# Sheet1.net
KiCad netlist of a schematic drawn in Altium Designer
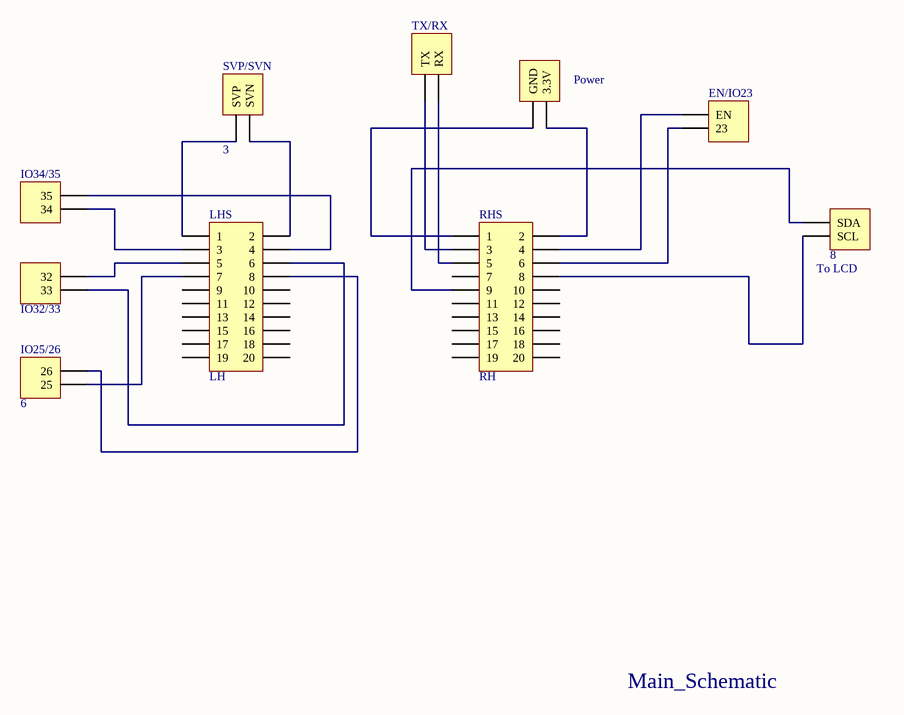
[diagram p0: Sheet1.SchDoc]

(export (version "E")
  (design (tool "Eeschema 10.0.6"))
  (components
    (comp (ref "EN/IO23")
      (value "7")
      (footprint "HDR1X2")
      (description "Header, 2-Pin")
      (fields (field (name "PUBLISHER") "Altium Limited"))
      (libsource (lib "") (part "Header 2H_3"))
    )
    (comp (ref "IO25/26")
      (value "6")
      (footprint "HDR1X2")
      (description "Header, 2-Pin")
      (fields (field (name "PUBLISHER") "Altium Limited"))
      (libsource (lib "") (part "Header 2H_4"))
    )
    (comp (ref "IO32/33")
      (value "5")
      (footprint "HDR1X2")
      (description "Header, 2-Pin")
      (fields (field (name "PUBLISHER") "Altium Limited"))
      (libsource (lib "") (part "Header 2H_4"))
    )
    (comp (ref "IO34/35")
      (value "4")
      (footprint "HDR1X2")
      (description "Header, 2-Pin")
      (fields (field (name "PUBLISHER") "Altium Limited"))
      (libsource (lib "") (part "Header 2H_4"))
    )
    (comp (ref "LHS")
      (value "LH")
      (footprint "HDR2X10")
      (description "Header, 10-Pin, Dual row")
      (fields (field (name "PUBLISHER") "Altium Limited"))
      (libsource (lib "University of Moratuwa") (part "Header 10X2H"))
    )
    (comp (ref "Power")
      (value "1")
      (footprint "HDR1X2")
      (description "Header, 2-Pin")
      (fields (field (name "PUBLISHER") "Altium Limited"))
      (libsource (lib "") (part "Header 2H_5"))
    )
    (comp (ref "RHS")
      (value "RH")
      (footprint "HDR2X10")
      (description "Header, 10-Pin, Dual row")
      (fields (field (name "PUBLISHER") "Altium Limited"))
      (libsource (lib "University of Moratuwa") (part "Header 10X2H"))
    )
    (comp (ref "SVP/SVN")
      (value "3")
      (footprint "HDR1X2")
      (description "Header, 2-Pin")
      (fields (field (name "PUBLISHER") "Altium Limited"))
      (libsource (lib "") (part "Header 2H_2"))
    )
    (comp (ref "To LCD")
      (value "8")
      (footprint "HDR1X2")
      (description "Header, 2-Pin")
      (fields (field (name "PUBLISHER") "Altium Limited"))
      (libsource (lib "University of Moratuwa") (part "Header 2H"))
    )
    (comp (ref "TX/RX")
      (value "2")
      (footprint "HDR1X2")
      (description "Header, 2-Pin")
      (fields (field (name "PUBLISHER") "Altium Limited"))
      (libsource (lib "") (part "Header 2H_1"))
    )
  )
  (nets
    (net (code "1") (name "Net-(EN/IO23-23)") (class "Default")
      (node (ref "EN/IO23") (pin "2") (pinfunction "23_2") (pintype "passive"))
      (node (ref "RHS") (pin "6") (pinfunction "6_6") (pintype "passive"))
    )
    (net (code "2") (name "Net-(EN/IO23-EN)") (class "Default")
      (node (ref "EN/IO23") (pin "1") (pinfunction "EN_1") (pintype "passive"))
      (node (ref "RHS") (pin "4") (pinfunction "4_4") (pintype "passive"))
    )
    (net (code "3") (name "Net-(IO25/26-25)") (class "Default")
      (node (ref "IO25/26") (pin "1") (pinfunction "25_1") (pintype "passive"))
      (node (ref "LHS") (pin "7") (pinfunction "7_7") (pintype "passive"))
    )
    (net (code "4") (name "Net-(IO25/26-26)") (class "Default")
      (node (ref "IO25/26") (pin "2") (pinfunction "26_2") (pintype "passive"))
      (node (ref "LHS") (pin "8") (pinfunction "8_8") (pintype "passive"))
    )
    (net (code "5") (name "Net-(IO32/33-25)") (class "Default")
      (node (ref "IO32/33") (pin "1") (pinfunction "25_1") (pintype "passive"))
      (node (ref "LHS") (pin "6") (pinfunction "6_6") (pintype "passive"))
    )
    (net (code "6") (name "Net-(IO32/33-26)") (class "Default")
      (node (ref "IO32/33") (pin "2") (pinfunction "26_2") (pintype "passive"))
      (node (ref "LHS") (pin "5") (pinfunction "5_5") (pintype "passive"))
    )
    (net (code "7") (name "Net-(IO34/35-25)") (class "Default")
      (node (ref "IO34/35") (pin "1") (pinfunction "25_1") (pintype "passive"))
      (node (ref "LHS") (pin "3") (pinfunction "3_3") (pintype "passive"))
    )
    (net (code "8") (name "Net-(IO34/35-26)") (class "Default")
      (node (ref "IO34/35") (pin "2") (pinfunction "26_2") (pintype "passive"))
      (node (ref "LHS") (pin "4") (pinfunction "4_4") (pintype "passive"))
    )
    (net (code "9") (name "Net-(Power-3.3V)") (class "Default")
      (node (ref "Power") (pin "2") (pinfunction "3.3V_2") (pintype "passive"))
      (node (ref "RHS") (pin "2") (pinfunction "2_2") (pintype "passive"))
    )
    (net (code "10") (name "Net-(Power-GND)") (class "Default")
      (node (ref "Power") (pin "1") (pinfunction "GND_1") (pintype "passive"))
      (node (ref "RHS") (pin "1") (pinfunction "1_1") (pintype "passive"))
    )
    (net (code "11") (name "Net-(SVP/SVN-SVN)") (class "Default")
      (node (ref "LHS") (pin "2") (pinfunction "2_2") (pintype "passive"))
      (node (ref "SVP/SVN") (pin "2") (pinfunction "SVN_2") (pintype "passive"))
    )
    (net (code "12") (name "Net-(SVP/SVN-SVP)") (class "Default")
      (node (ref "LHS") (pin "1") (pinfunction "1_1") (pintype "passive"))
      (node (ref "SVP/SVN") (pin "1") (pinfunction "SVP_1") (pintype "passive"))
    )
    (net (code "13") (name "Net-(TX/RX-RX)") (class "Default")
      (node (ref "RHS") (pin "5") (pinfunction "5_5") (pintype "passive"))
      (node (ref "TX/RX") (pin "2") (pinfunction "RX_2") (pintype "passive"))
    )
    (net (code "14") (name "Net-(TX/RX-TX)") (class "Default")
      (node (ref "RHS") (pin "3") (pinfunction "3_3") (pintype "passive"))
      (node (ref "TX/RX") (pin "1") (pinfunction "TX_1") (pintype "passive"))
    )
    (net (code "15") (name "Net-(To LCD-SCL)") (class "Default")
      (node (ref "RHS") (pin "8") (pinfunction "8_8") (pintype "passive"))
      (node (ref "To LCD") (pin "2") (pinfunction "SCL_2") (pintype "passive"))
    )
    (net (code "16") (name "Net-(To LCD-SDA)") (class "Default")
      (node (ref "RHS") (pin "9") (pinfunction "9_9") (pintype "passive"))
      (node (ref "To LCD") (pin "1") (pinfunction "SDA_1") (pintype "passive"))
    )
    (net (code "17") (name "unconnected-(LHS-Pad9)") (class "Default")
      (node (ref "LHS") (pin "9") (pinfunction "9_9") (pintype "passive"))
    )
    (net (code "18") (name "unconnected-(LHS-Pad10)") (class "Default")
      (node (ref "LHS") (pin "10") (pinfunction "10_10") (pintype "passive"))
    )
    (net (code "19") (name "unconnected-(LHS-Pad11)") (class "Default")
      (node (ref "LHS") (pin "11") (pinfunction "11_11") (pintype "passive"))
    )
    (net (code "20") (name "unconnected-(LHS-Pad12)") (class "Default")
      (node (ref "LHS") (pin "12") (pinfunction "12_12") (pintype "passive"))
    )
    (net (code "21") (name "unconnected-(LHS-Pad13)") (class "Default")
      (node (ref "LHS") (pin "13") (pinfunction "13_13") (pintype "passive"))
    )
    (net (code "22") (name "unconnected-(LHS-Pad14)") (class "Default")
      (node (ref "LHS") (pin "14") (pinfunction "14_14") (pintype "passive"))
    )
    (net (code "23") (name "unconnected-(LHS-Pad15)") (class "Default")
      (node (ref "LHS") (pin "15") (pinfunction "15_15") (pintype "passive"))
    )
    (net (code "24") (name "unconnected-(LHS-Pad16)") (class "Default")
      (node (ref "LHS") (pin "16") (pinfunction "16_16") (pintype "passive"))
    )
    (net (code "25") (name "unconnected-(LHS-Pad17)") (class "Default")
      (node (ref "LHS") (pin "17") (pinfunction "17_17") (pintype "passive"))
    )
    (net (code "26") (name "unconnected-(LHS-Pad18)") (class "Default")
      (node (ref "LHS") (pin "18") (pinfunction "18_18") (pintype "passive"))
    )
    (net (code "27") (name "unconnected-(LHS-Pad19)") (class "Default")
      (node (ref "LHS") (pin "19") (pinfunction "19_19") (pintype "passive"))
    )
    (net (code "28") (name "unconnected-(LHS-Pad20)") (class "Default")
      (node (ref "LHS") (pin "20") (pinfunction "20_20") (pintype "passive"))
    )
    (net (code "29") (name "unconnected-(RHS-Pad7)") (class "Default")
      (node (ref "RHS") (pin "7") (pinfunction "7_7") (pintype "passive"))
    )
    (net (code "30") (name "unconnected-(RHS-Pad10)") (class "Default")
      (node (ref "RHS") (pin "10") (pinfunction "10_10") (pintype "passive"))
    )
    (net (code "31") (name "unconnected-(RHS-Pad11)") (class "Default")
      (node (ref "RHS") (pin "11") (pinfunction "11_11") (pintype "passive"))
    )
    (net (code "32") (name "unconnected-(RHS-Pad12)") (class "Default")
      (node (ref "RHS") (pin "12") (pinfunction "12_12") (pintype "passive"))
    )
    (net (code "33") (name "unconnected-(RHS-Pad13)") (class "Default")
      (node (ref "RHS") (pin "13") (pinfunction "13_13") (pintype "passive"))
    )
    (net (code "34") (name "unconnected-(RHS-Pad14)") (class "Default")
      (node (ref "RHS") (pin "14") (pinfunction "14_14") (pintype "passive"))
    )
    (net (code "35") (name "unconnected-(RHS-Pad15)") (class "Default")
      (node (ref "RHS") (pin "15") (pinfunction "15_15") (pintype "passive"))
    )
    (net (code "36") (name "unconnected-(RHS-Pad16)") (class "Default")
      (node (ref "RHS") (pin "16") (pinfunction "16_16") (pintype "passive"))
    )
    (net (code "37") (name "unconnected-(RHS-Pad17)") (class "Default")
      (node (ref "RHS") (pin "17") (pinfunction "17_17") (pintype "passive"))
    )
    (net (code "38") (name "unconnected-(RHS-Pad18)") (class "Default")
      (node (ref "RHS") (pin "18") (pinfunction "18_18") (pintype "passive"))
    )
    (net (code "39") (name "unconnected-(RHS-Pad19)") (class "Default")
      (node (ref "RHS") (pin "19") (pinfunction "19_19") (pintype "passive"))
    )
    (net (code "40") (name "unconnected-(RHS-Pad20)") (class "Default")
      (node (ref "RHS") (pin "20") (pinfunction "20_20") (pintype "passive"))
    )
  )
)
